# mainModule.net
KiCad netlist of a schematic drawn in EAGLE
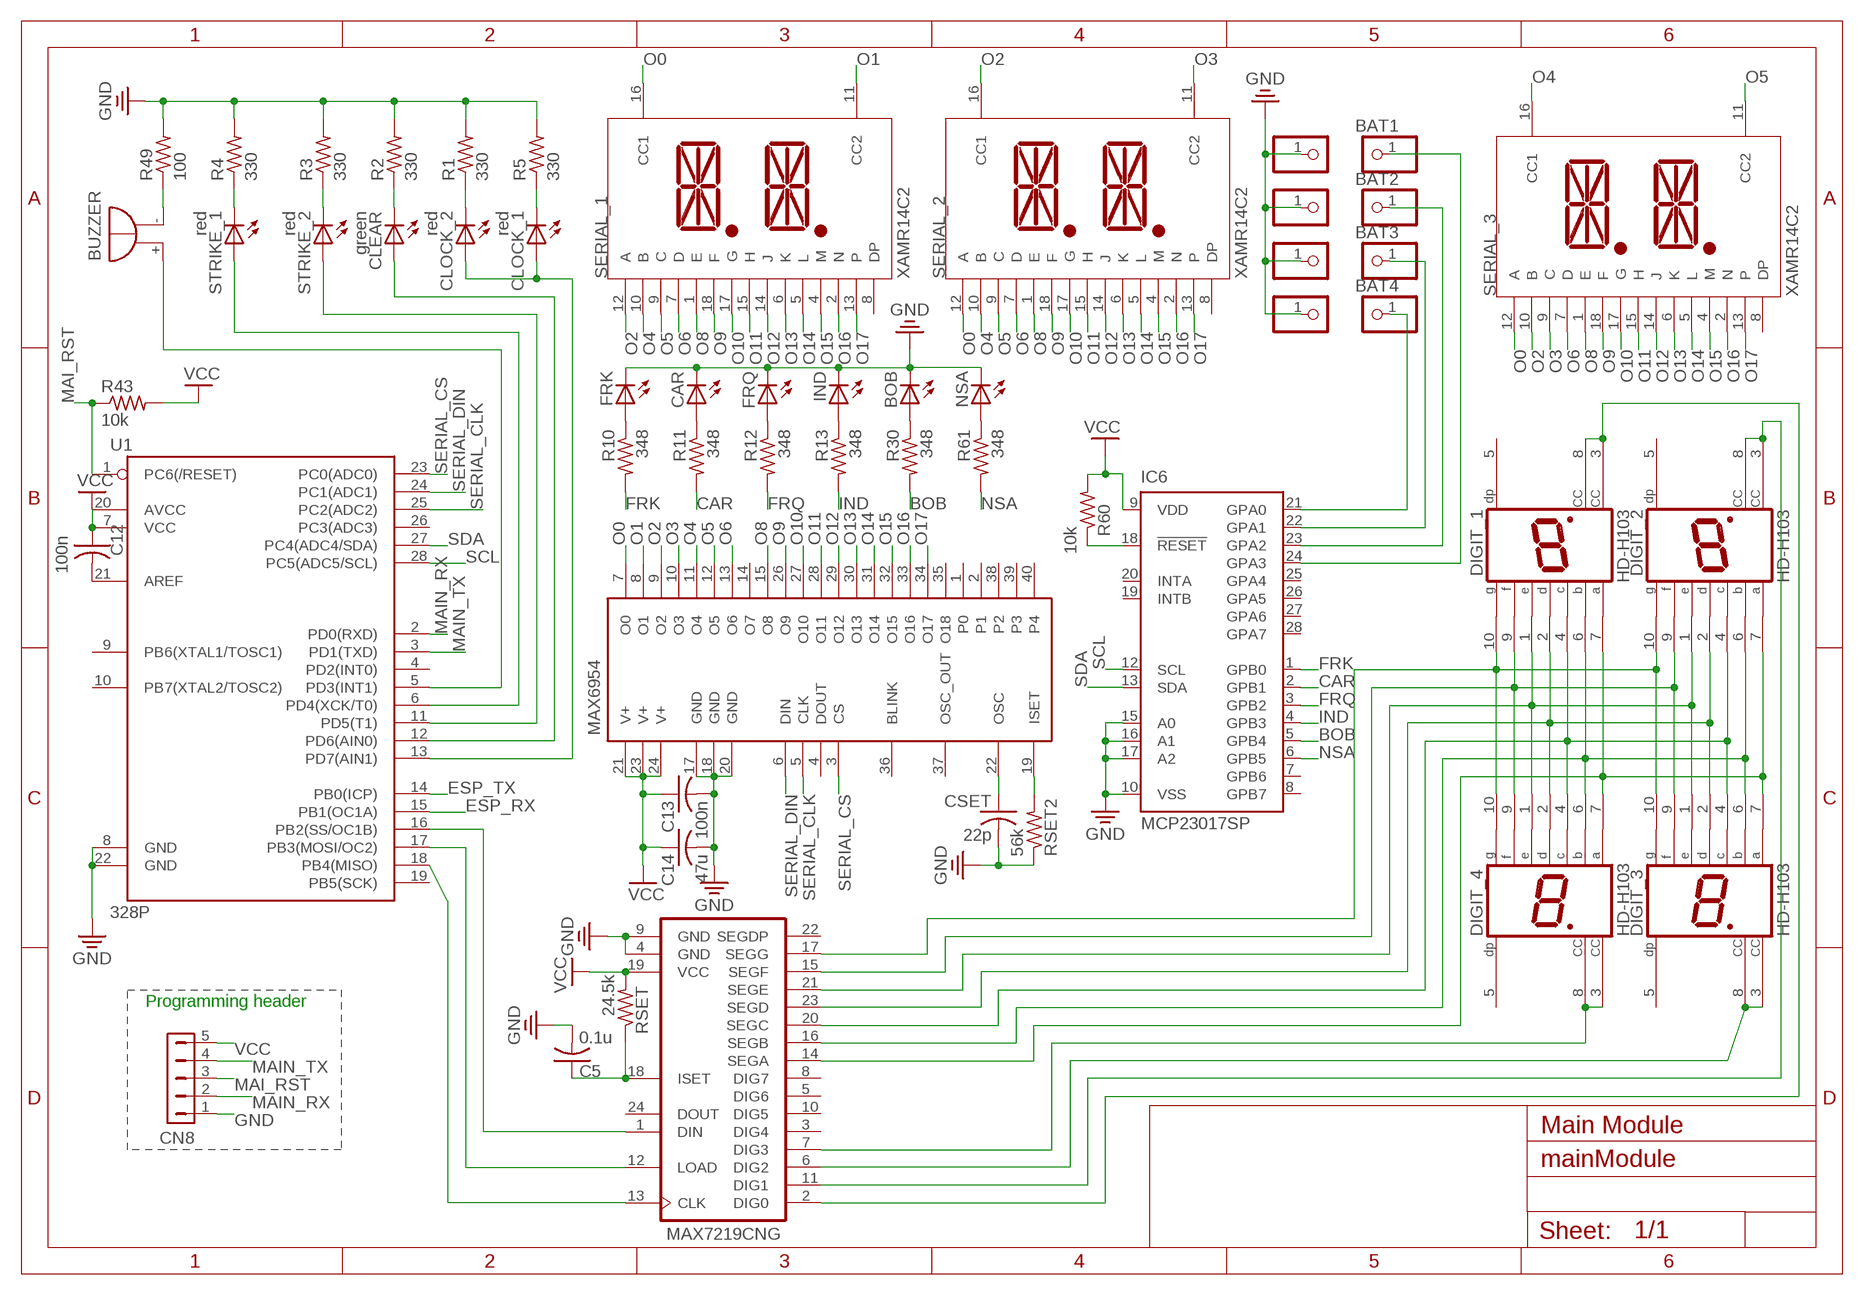
[diagram p0: schematic, sheet 1]

(export (version "E")
  (design (tool "Eeschema 10.0.6"))
  (components
    (comp (ref "BAT1")
      (value "PINHD-1X1")
      (footprint "eagle-import:1X01")
      (libsource (lib "eagle-import") (part "PINHD-1X1"))
    )
    (comp (ref "BAT2")
      (value "PINHD-1X1")
      (footprint "eagle-import:1X01")
      (libsource (lib "eagle-import") (part "PINHD-1X1"))
    )
    (comp (ref "BAT3")
      (value "PINHD-1X1")
      (footprint "eagle-import:1X01")
      (libsource (lib "eagle-import") (part "PINHD-1X1"))
    )
    (comp (ref "BAT4")
      (value "PINHD-1X1")
      (footprint "eagle-import:1X01")
      (libsource (lib "eagle-import") (part "PINHD-1X1"))
    )
    (comp (ref "BOB")
      (value "LED5MM")
      (footprint "eagle-import:LED5MM")
      (libsource (lib "eagle-import") (part "LED5MM"))
    )
    (comp (ref "BUZZER")
      (value "EB2209A")
      (footprint "eagle-import:EB2209A")
      (libsource (lib "eagle-import") (part "EB2209A"))
    )
    (comp (ref "C5")
      (value "0.1u")
      (footprint "eagle-import:C025-024X044")
      (libsource (lib "eagle-import") (part "C-US025-024X044"))
    )
    (comp (ref "C12")
      (value "100n")
      (footprint "eagle-import:C025-024X044")
      (libsource (lib "eagle-import") (part "C-US025-024X044"))
    )
    (comp (ref "C13")
      (value "100n")
      (footprint "eagle-import:C025-024X044")
      (libsource (lib "eagle-import") (part "C-US025-024X044"))
    )
    (comp (ref "C14")
      (value "47u")
      (footprint "eagle-import:C025-024X044")
      (libsource (lib "eagle-import") (part "C-US025-024X044"))
    )
    (comp (ref "CAR")
      (value "LED5MM")
      (footprint "eagle-import:LED5MM")
      (libsource (lib "eagle-import") (part "LED5MM"))
    )
    (comp (ref "CLEAR")
      (value "green")
      (footprint "eagle-import:LED5MM")
      (libsource (lib "eagle-import") (part "LED5MM"))
    )
    (comp (ref "CLOCK_1")
      (value "red")
      (footprint "eagle-import:LED5MM")
      (libsource (lib "eagle-import") (part "LED5MM"))
    )
    (comp (ref "CLOCK_2")
      (value "red")
      (footprint "eagle-import:LED5MM")
      (libsource (lib "eagle-import") (part "LED5MM"))
    )
    (comp (ref "CN8")
      (value "HDR-1X5-SIP-100")
      (footprint "eagle-import:SIP-100-5V")
      (libsource (lib "eagle-import") (part "HDR-1X5-SIP-100"))
    )
    (comp (ref "CSET")
      (value "22p")
      (footprint "eagle-import:C025-024X044")
      (libsource (lib "eagle-import") (part "C-US025-024X044"))
    )
    (comp (ref "DIGIT_1")
      (value "HD-H103")
      (footprint "eagle-import:HDSP-M")
      (libsource (lib "eagle-import") (part "HD-H103"))
    )
    (comp (ref "DIGIT_2")
      (value "HD-H103")
      (footprint "eagle-import:HDSP-M")
      (libsource (lib "eagle-import") (part "HD-H103"))
    )
    (comp (ref "DIGIT_3")
      (value "HD-H103")
      (footprint "eagle-import:HDSP-M")
      (libsource (lib "eagle-import") (part "HD-H103"))
    )
    (comp (ref "DIGIT_4")
      (value "HD-H103")
      (footprint "eagle-import:HDSP-M")
      (libsource (lib "eagle-import") (part "HD-H103"))
    )
    (comp (ref "FRK")
      (value "LED5MM")
      (footprint "eagle-import:LED5MM")
      (libsource (lib "eagle-import") (part "LED5MM"))
    )
    (comp (ref "FRQ")
      (value "LED5MM")
      (footprint "eagle-import:LED5MM")
      (libsource (lib "eagle-import") (part "LED5MM"))
    )
    (comp (ref "IC1")
      (value "MAX7219CNG")
      (footprint "eagle-import:DIL24-3")
      (fields (field (name "MF") "MAXIM"))
      (libsource (lib "eagle-import") (part "MAX7219CNG"))
    )
    (comp (ref "IC6")
      (value "MCP23017SP")
      (footprint "eagle-import:DIL28-3")
      (libsource (lib "eagle-import") (part "MCP23017SP"))
    )
    (comp (ref "IND")
      (value "LED5MM")
      (footprint "eagle-import:LED5MM")
      (libsource (lib "eagle-import") (part "LED5MM"))
    )
    (comp (ref "JP17")
      (value "PINHD-1X1")
      (footprint "eagle-import:1X01")
      (libsource (lib "eagle-import") (part "PINHD-1X1"))
    )
    (comp (ref "JP18")
      (value "PINHD-1X1")
      (footprint "eagle-import:1X01")
      (libsource (lib "eagle-import") (part "PINHD-1X1"))
    )
    (comp (ref "JP19")
      (value "PINHD-1X1")
      (footprint "eagle-import:1X01")
      (libsource (lib "eagle-import") (part "PINHD-1X1"))
    )
    (comp (ref "JP20")
      (value "PINHD-1X1")
      (footprint "eagle-import:1X01")
      (libsource (lib "eagle-import") (part "PINHD-1X1"))
    )
    (comp (ref "MAX6954")
      (value "MAX6954")
      (footprint "eagle-import:MAX6954")
      (libsource (lib "eagle-import") (part "MAX6954"))
    )
    (comp (ref "NSA")
      (value "LED5MM")
      (footprint "eagle-import:LED5MM")
      (libsource (lib "eagle-import") (part "LED5MM"))
    )
    (comp (ref "R1")
      (value "330")
      (footprint "eagle-import:0309_12")
      (libsource (lib "eagle-import") (part "adafruit_420_R-US_0309/12"))
    )
    (comp (ref "R2")
      (value "330")
      (footprint "eagle-import:0309_12")
      (libsource (lib "eagle-import") (part "adafruit_420_R-US_0309/12"))
    )
    (comp (ref "R3")
      (value "330")
      (footprint "eagle-import:0309_12")
      (libsource (lib "eagle-import") (part "adafruit_420_R-US_0309/12"))
    )
    (comp (ref "R4")
      (value "330")
      (footprint "eagle-import:0309_12")
      (libsource (lib "eagle-import") (part "adafruit_420_R-US_0309/12"))
    )
    (comp (ref "R5")
      (value "330")
      (footprint "eagle-import:0309_12")
      (libsource (lib "eagle-import") (part "adafruit_420_R-US_0309/12"))
    )
    (comp (ref "R10")
      (value "348")
      (footprint "eagle-import:0204_7")
      (libsource (lib "eagle-import") (part "R-US_0204/7"))
    )
    (comp (ref "R11")
      (value "348")
      (footprint "eagle-import:0204_7")
      (libsource (lib "eagle-import") (part "R-US_0204/7"))
    )
    (comp (ref "R12")
      (value "348")
      (footprint "eagle-import:0204_7")
      (libsource (lib "eagle-import") (part "R-US_0204/7"))
    )
    (comp (ref "R13")
      (value "348")
      (footprint "eagle-import:0204_7")
      (libsource (lib "eagle-import") (part "R-US_0204/7"))
    )
    (comp (ref "R30")
      (value "348")
      (footprint "eagle-import:0204_7")
      (libsource (lib "eagle-import") (part "R-US_0204/7"))
    )
    (comp (ref "R43")
      (value "10k")
      (footprint "eagle-import:0309_12")
      (libsource (lib "eagle-import") (part "adafruit_420_R-US_0309/12"))
    )
    (comp (ref "R49")
      (value "100")
      (footprint "eagle-import:0309_12")
      (libsource (lib "eagle-import") (part "adafruit_420_R-US_0309/12"))
    )
    (comp (ref "R60")
      (value "10k")
      (footprint "eagle-import:0204_7")
      (libsource (lib "eagle-import") (part "R-US_0204/7"))
    )
    (comp (ref "R61")
      (value "348")
      (footprint "eagle-import:0204_7")
      (libsource (lib "eagle-import") (part "R-US_0204/7"))
    )
    (comp (ref "RSET")
      (value "24.5k")
      (footprint "eagle-import:0204_7")
      (libsource (lib "eagle-import") (part "R-US_0204/7"))
    )
    (comp (ref "RSET2")
      (value "56k")
      (footprint "eagle-import:0204_7")
      (libsource (lib "eagle-import") (part "R-US_0204/7"))
    )
    (comp (ref "SERIAL_1")
      (value "XAMR14C2")
      (footprint "eagle-import:XAMR14C2")
      (libsource (lib "eagle-import") (part "XAMR14C2"))
    )
    (comp (ref "SERIAL_2")
      (value "XAMR14C2")
      (footprint "eagle-import:XAMR14C2")
      (libsource (lib "eagle-import") (part "XAMR14C2"))
    )
    (comp (ref "SERIAL_3")
      (value "XAMR14C2")
      (footprint "eagle-import:XAMR14C2")
      (libsource (lib "eagle-import") (part "XAMR14C2"))
    )
    (comp (ref "STRIKE_1")
      (value "red")
      (footprint "eagle-import:LED5MM")
      (libsource (lib "eagle-import") (part "LED5MM"))
    )
    (comp (ref "STRIKE_2")
      (value "red")
      (footprint "eagle-import:LED5MM")
      (libsource (lib "eagle-import") (part "LED5MM"))
    )
    (comp (ref "U1")
      (value "328P")
      (footprint "eagle-import:DIP28")
      (libsource (lib "eagle-import") (part "ATMEGA328P_PDIP"))
    )
  )
  (nets
    (net (code "1") (name "/BOB") (class "Default")
      (node (ref "IC6") (pin "5") (pinfunction "GPB4_5") (pintype "bidirectional"))
      (node (ref "R30") (pin "2") (pinfunction "2_2") (pintype "passive"))
    )
    (net (code "2") (name "/CAR") (class "Default")
      (node (ref "IC6") (pin "2") (pinfunction "GPB1_2") (pintype "bidirectional"))
      (node (ref "R11") (pin "2") (pinfunction "2_2") (pintype "passive"))
    )
    (net (code "3") (name "/ESP_RX") (class "Default")
      (node (ref "U1") (pin "15") (pinfunction "PB1(OC1A)_15") (pintype "bidirectional"))
    )
    (net (code "4") (name "/ESP_TX") (class "Default")
      (node (ref "U1") (pin "14") (pinfunction "PB0(ICP)_14") (pintype "bidirectional"))
    )
    (net (code "5") (name "/FRK") (class "Default")
      (node (ref "IC6") (pin "1") (pinfunction "GPB0_1") (pintype "bidirectional"))
      (node (ref "R10") (pin "2") (pinfunction "2_2") (pintype "passive"))
    )
    (net (code "6") (name "/FRQ") (class "Default")
      (node (ref "IC6") (pin "3") (pinfunction "GPB2_3") (pintype "bidirectional"))
      (node (ref "R12") (pin "2") (pinfunction "2_2") (pintype "passive"))
    )
    (net (code "7") (name "/IND") (class "Default")
      (node (ref "IC6") (pin "4") (pinfunction "GPB3_4") (pintype "bidirectional"))
      (node (ref "R13") (pin "2") (pinfunction "2_2") (pintype "passive"))
    )
    (net (code "8") (name "/MAIN_RX") (class "Default")
      (node (ref "CN8") (pin "2") (pinfunction "2_2") (pintype "passive"))
      (node (ref "U1") (pin "2") (pinfunction "PD0(RXD)_2") (pintype "bidirectional"))
    )
    (net (code "9") (name "/MAIN_TX") (class "Default")
      (node (ref "CN8") (pin "4") (pinfunction "4_4") (pintype "passive"))
      (node (ref "U1") (pin "3") (pinfunction "PD1(TXD)_3") (pintype "bidirectional"))
    )
    (net (code "10") (name "/MAI_RST") (class "Default")
      (node (ref "CN8") (pin "3") (pinfunction "3_3") (pintype "passive"))
      (node (ref "R43") (pin "1") (pinfunction "1_1") (pintype "passive"))
      (node (ref "U1") (pin "1") (pinfunction "PC6(/RESET)_1") (pintype "bidirectional"))
    )
    (net (code "11") (name "/NSA") (class "Default")
      (node (ref "IC6") (pin "6") (pinfunction "GPB5_6") (pintype "bidirectional"))
      (node (ref "R61") (pin "2") (pinfunction "2_2") (pintype "passive"))
    )
    (net (code "12") (name "/O0") (class "Default")
      (node (ref "MAX6954") (pin "7") (pinfunction "O0_7") (pintype "bidirectional"))
      (node (ref "SERIAL_1") (pin "16") (pinfunction "CC1_16") (pintype "bidirectional"))
      (node (ref "SERIAL_2") (pin "12") (pinfunction "A_12") (pintype "bidirectional"))
      (node (ref "SERIAL_3") (pin "12") (pinfunction "A_12") (pintype "bidirectional"))
    )
    (net (code "13") (name "/O1") (class "Default")
      (node (ref "MAX6954") (pin "8") (pinfunction "O1_8") (pintype "bidirectional"))
      (node (ref "SERIAL_1") (pin "11") (pinfunction "CC2_11") (pintype "bidirectional"))
    )
    (net (code "14") (name "/O2") (class "Default")
      (node (ref "MAX6954") (pin "9") (pinfunction "O2_9") (pintype "bidirectional"))
      (node (ref "SERIAL_1") (pin "12") (pinfunction "A_12") (pintype "bidirectional"))
      (node (ref "SERIAL_2") (pin "16") (pinfunction "CC1_16") (pintype "bidirectional"))
      (node (ref "SERIAL_3") (pin "10") (pinfunction "B_10") (pintype "bidirectional"))
    )
    (net (code "15") (name "/O3") (class "Default")
      (node (ref "MAX6954") (pin "10") (pinfunction "O3_10") (pintype "bidirectional"))
      (node (ref "SERIAL_2") (pin "11") (pinfunction "CC2_11") (pintype "bidirectional"))
      (node (ref "SERIAL_3") (pin "9") (pinfunction "C_9") (pintype "bidirectional"))
    )
    (net (code "16") (name "/O4") (class "Default")
      (node (ref "MAX6954") (pin "11") (pinfunction "O4_11") (pintype "bidirectional"))
      (node (ref "SERIAL_1") (pin "10") (pinfunction "B_10") (pintype "bidirectional"))
      (node (ref "SERIAL_2") (pin "10") (pinfunction "B_10") (pintype "bidirectional"))
      (node (ref "SERIAL_3") (pin "16") (pinfunction "CC1_16") (pintype "bidirectional"))
    )
    (net (code "17") (name "/O5") (class "Default")
      (node (ref "MAX6954") (pin "12") (pinfunction "O5_12") (pintype "bidirectional"))
      (node (ref "SERIAL_1") (pin "9") (pinfunction "C_9") (pintype "bidirectional"))
      (node (ref "SERIAL_2") (pin "9") (pinfunction "C_9") (pintype "bidirectional"))
      (node (ref "SERIAL_3") (pin "11") (pinfunction "CC2_11") (pintype "bidirectional"))
    )
    (net (code "18") (name "/O6") (class "Default")
      (node (ref "MAX6954") (pin "13") (pinfunction "O6_13") (pintype "bidirectional"))
      (node (ref "SERIAL_1") (pin "7") (pinfunction "D_7") (pintype "bidirectional"))
      (node (ref "SERIAL_2") (pin "7") (pinfunction "D_7") (pintype "bidirectional"))
      (node (ref "SERIAL_3") (pin "7") (pinfunction "D_7") (pintype "bidirectional"))
    )
    (net (code "19") (name "/O8") (class "Default")
      (node (ref "MAX6954") (pin "15") (pinfunction "O8_15") (pintype "bidirectional"))
      (node (ref "SERIAL_1") (pin "1") (pinfunction "E_1") (pintype "bidirectional"))
      (node (ref "SERIAL_2") (pin "1") (pinfunction "E_1") (pintype "bidirectional"))
      (node (ref "SERIAL_3") (pin "1") (pinfunction "E_1") (pintype "bidirectional"))
    )
    (net (code "20") (name "/O9") (class "Default")
      (node (ref "MAX6954") (pin "26") (pinfunction "O9_26") (pintype "bidirectional"))
      (node (ref "SERIAL_1") (pin "18") (pinfunction "F_18") (pintype "bidirectional"))
      (node (ref "SERIAL_2") (pin "18") (pinfunction "F_18") (pintype "bidirectional"))
      (node (ref "SERIAL_3") (pin "18") (pinfunction "F_18") (pintype "bidirectional"))
    )
    (net (code "21") (name "/O10") (class "Default")
      (node (ref "MAX6954") (pin "27") (pinfunction "O10_27") (pintype "bidirectional"))
      (node (ref "SERIAL_1") (pin "17") (pinfunction "G_17") (pintype "bidirectional"))
      (node (ref "SERIAL_2") (pin "17") (pinfunction "G_17") (pintype "bidirectional"))
      (node (ref "SERIAL_3") (pin "17") (pinfunction "G_17") (pintype "bidirectional"))
    )
    (net (code "22") (name "/O11") (class "Default")
      (node (ref "MAX6954") (pin "28") (pinfunction "O11_28") (pintype "bidirectional"))
      (node (ref "SERIAL_1") (pin "15") (pinfunction "H_15") (pintype "bidirectional"))
      (node (ref "SERIAL_2") (pin "15") (pinfunction "H_15") (pintype "bidirectional"))
      (node (ref "SERIAL_3") (pin "15") (pinfunction "H_15") (pintype "bidirectional"))
    )
    (net (code "23") (name "/O12") (class "Default")
      (node (ref "MAX6954") (pin "29") (pinfunction "O12_29") (pintype "bidirectional"))
      (node (ref "SERIAL_1") (pin "14") (pinfunction "J_14") (pintype "bidirectional"))
      (node (ref "SERIAL_2") (pin "14") (pinfunction "J_14") (pintype "bidirectional"))
      (node (ref "SERIAL_3") (pin "14") (pinfunction "J_14") (pintype "bidirectional"))
    )
    (net (code "24") (name "/O13") (class "Default")
      (node (ref "MAX6954") (pin "30") (pinfunction "O13_30") (pintype "bidirectional"))
      (node (ref "SERIAL_1") (pin "6") (pinfunction "K_6") (pintype "bidirectional"))
      (node (ref "SERIAL_2") (pin "6") (pinfunction "K_6") (pintype "bidirectional"))
      (node (ref "SERIAL_3") (pin "6") (pinfunction "K_6") (pintype "bidirectional"))
    )
    (net (code "25") (name "/O14") (class "Default")
      (node (ref "MAX6954") (pin "31") (pinfunction "O14_31") (pintype "bidirectional"))
      (node (ref "SERIAL_1") (pin "5") (pinfunction "L_5") (pintype "bidirectional"))
      (node (ref "SERIAL_2") (pin "5") (pinfunction "L_5") (pintype "bidirectional"))
      (node (ref "SERIAL_3") (pin "5") (pinfunction "L_5") (pintype "bidirectional"))
    )
    (net (code "26") (name "/O15") (class "Default")
      (node (ref "MAX6954") (pin "32") (pinfunction "O15_32") (pintype "bidirectional"))
      (node (ref "SERIAL_1") (pin "4") (pinfunction "M_4") (pintype "bidirectional"))
      (node (ref "SERIAL_2") (pin "4") (pinfunction "M_4") (pintype "bidirectional"))
      (node (ref "SERIAL_3") (pin "4") (pinfunction "M_4") (pintype "bidirectional"))
    )
    (net (code "27") (name "/O16") (class "Default")
      (node (ref "MAX6954") (pin "33") (pinfunction "O16_33") (pintype "bidirectional"))
      (node (ref "SERIAL_1") (pin "2") (pinfunction "N_2") (pintype "bidirectional"))
      (node (ref "SERIAL_2") (pin "2") (pinfunction "N_2") (pintype "bidirectional"))
      (node (ref "SERIAL_3") (pin "2") (pinfunction "N_2") (pintype "bidirectional"))
    )
    (net (code "28") (name "/O17") (class "Default")
      (node (ref "MAX6954") (pin "34") (pinfunction "O17_34") (pintype "bidirectional"))
      (node (ref "SERIAL_1") (pin "13") (pinfunction "P_13") (pintype "bidirectional"))
      (node (ref "SERIAL_2") (pin "13") (pinfunction "P_13") (pintype "bidirectional"))
      (node (ref "SERIAL_3") (pin "13") (pinfunction "P_13") (pintype "bidirectional"))
    )
    (net (code "29") (name "/SCL") (class "Default")
      (node (ref "IC6") (pin "12") (pinfunction "SCL_12") (pintype "input"))
      (node (ref "U1") (pin "28") (pinfunction "PC5(ADC5/SCL)_28") (pintype "bidirectional"))
    )
    (net (code "30") (name "/SDA") (class "Default")
      (node (ref "IC6") (pin "13") (pinfunction "SDA_13") (pintype "bidirectional"))
      (node (ref "U1") (pin "27") (pinfunction "PC4(ADC4/SDA)_27") (pintype "bidirectional"))
    )
    (net (code "31") (name "/SERIAL_CLK") (class "Default")
      (node (ref "MAX6954") (pin "5") (pinfunction "CLK_5") (pintype "bidirectional"))
      (node (ref "U1") (pin "25") (pinfunction "PC2(ADC2)_25") (pintype "bidirectional"))
    )
    (net (code "32") (name "/SERIAL_CS") (class "Default")
      (node (ref "MAX6954") (pin "3") (pinfunction "CS_3") (pintype "bidirectional"))
      (node (ref "U1") (pin "23") (pinfunction "PC0(ADC0)_23") (pintype "bidirectional"))
    )
    (net (code "33") (name "/SERIAL_DIN") (class "Default")
      (node (ref "MAX6954") (pin "6") (pinfunction "DIN_6") (pintype "bidirectional"))
      (node (ref "U1") (pin "24") (pinfunction "PC1(ADC1)_24") (pintype "bidirectional"))
    )
    (net (code "34") (name "GND") (class "Default")
      (node (ref "BOB") (pin "K") (pinfunction "C_K") (pintype "passive"))
      (node (ref "C13") (pin "2") (pinfunction "2_2") (pintype "passive"))
      (node (ref "C14") (pin "2") (pinfunction "2_2") (pintype "passive"))
      (node (ref "C5") (pin "2") (pinfunction "2_2") (pintype "passive"))
      (node (ref "CAR") (pin "K") (pinfunction "C_K") (pintype "passive"))
      (node (ref "CN8") (pin "1") (pinfunction "1_1") (pintype "passive"))
      (node (ref "CSET") (pin "2") (pinfunction "2_2") (pintype "passive"))
      (node (ref "FRK") (pin "K") (pinfunction "C_K") (pintype "passive"))
      (node (ref "FRQ") (pin "K") (pinfunction "C_K") (pintype "passive"))
      (node (ref "IC1") (pin "4") (pinfunction "GND_4") (pintype "power_in"))
      (node (ref "IC1") (pin "9") (pinfunction "GND_9") (pintype "power_in"))
      (node (ref "IC6") (pin "10") (pinfunction "VSS_10") (pintype "power_in"))
      (node (ref "IC6") (pin "15") (pinfunction "A0_15") (pintype "input"))
      (node (ref "IC6") (pin "16") (pinfunction "A1_16") (pintype "input"))
      (node (ref "IC6") (pin "17") (pinfunction "A2_17") (pintype "input"))
      (node (ref "IND") (pin "K") (pinfunction "C_K") (pintype "passive"))
      (node (ref "JP17") (pin "1") (pinfunction "1_1") (pintype "passive"))
      (node (ref "JP18") (pin "1") (pinfunction "1_1") (pintype "passive"))
      (node (ref "JP19") (pin "1") (pinfunction "1_1") (pintype "passive"))
      (node (ref "JP20") (pin "1") (pinfunction "1_1") (pintype "passive"))
      (node (ref "MAX6954") (pin "17") (pinfunction "GND_17") (pintype "bidirectional"))
      (node (ref "MAX6954") (pin "18") (pinfunction "GND_18") (pintype "bidirectional"))
      (node (ref "MAX6954") (pin "20") (pinfunction "GND_20") (pintype "bidirectional"))
      (node (ref "NSA") (pin "K") (pinfunction "C_K") (pintype "passive"))
      (node (ref "R1") (pin "2") (pinfunction "2_2") (pintype "passive"))
      (node (ref "R2") (pin "2") (pinfunction "2_2") (pintype "passive"))
      (node (ref "R3") (pin "2") (pinfunction "2_2") (pintype "passive"))
      (node (ref "R4") (pin "2") (pinfunction "2_2") (pintype "passive"))
      (node (ref "R49") (pin "2") (pinfunction "2_2") (pintype "passive"))
      (node (ref "R5") (pin "2") (pinfunction "2_2") (pintype "passive"))
      (node (ref "RSET2") (pin "1") (pinfunction "1_1") (pintype "passive"))
      (node (ref "U1") (pin "22") (pinfunction "GND_22") (pintype "bidirectional"))
      (node (ref "U1") (pin "8") (pinfunction "GND_8") (pintype "bidirectional"))
    )
    (net (code "35") (name "Net-(BOB-PadA)") (class "Default")
      (node (ref "BOB") (pin "A") (pinfunction "A_A") (pintype "passive"))
      (node (ref "R30") (pin "1") (pinfunction "1_1") (pintype "passive"))
    )
    (net (code "36") (name "Net-(BUZZER-Pad-)") (class "Default")
      (node (ref "BUZZER") (pin "-") (pinfunction "-_-") (pintype "passive"))
      (node (ref "R49") (pin "1") (pinfunction "1_1") (pintype "passive"))
    )
    (net (code "37") (name "Net-(CAR-PadA)") (class "Default")
      (node (ref "CAR") (pin "A") (pinfunction "A_A") (pintype "passive"))
      (node (ref "R11") (pin "1") (pinfunction "1_1") (pintype "passive"))
    )
    (net (code "38") (name "Net-(CLEAR-C)") (class "Default")
      (node (ref "CLEAR") (pin "K") (pinfunction "C_K") (pintype "passive"))
      (node (ref "R2") (pin "1") (pinfunction "1_1") (pintype "passive"))
    )
    (net (code "39") (name "Net-(CLOCK_1-C)") (class "Default")
      (node (ref "CLOCK_1") (pin "K") (pinfunction "C_K") (pintype "passive"))
      (node (ref "R5") (pin "1") (pinfunction "1_1") (pintype "passive"))
    )
    (net (code "40") (name "Net-(CLOCK_2-C)") (class "Default")
      (node (ref "CLOCK_2") (pin "K") (pinfunction "C_K") (pintype "passive"))
      (node (ref "R1") (pin "1") (pinfunction "1_1") (pintype "passive"))
    )
    (net (code "41") (name "Net-(DIGIT_1-A)") (class "Default")
      (node (ref "DIGIT_1") (pin "7") (pinfunction "A_7") (pintype "passive"))
      (node (ref "DIGIT_2") (pin "7") (pinfunction "A_7") (pintype "passive"))
      (node (ref "DIGIT_3") (pin "7") (pinfunction "A_7") (pintype "passive"))
      (node (ref "DIGIT_4") (pin "7") (pinfunction "A_7") (pintype "passive"))
      (node (ref "IC1") (pin "14") (pinfunction "SEGA_14") (pintype "output"))
    )
    (net (code "42") (name "Net-(DIGIT_1-B)") (class "Default")
      (node (ref "DIGIT_1") (pin "6") (pinfunction "B_6") (pintype "passive"))
      (node (ref "DIGIT_2") (pin "6") (pinfunction "B_6") (pintype "passive"))
      (node (ref "DIGIT_3") (pin "6") (pinfunction "B_6") (pintype "passive"))
      (node (ref "DIGIT_4") (pin "6") (pinfunction "B_6") (pintype "passive"))
      (node (ref "IC1") (pin "16") (pinfunction "SEGB_16") (pintype "output"))
    )
    (net (code "43") (name "Net-(DIGIT_1-C)") (class "Default")
      (node (ref "DIGIT_1") (pin "4") (pinfunction "C_4") (pintype "passive"))
      (node (ref "DIGIT_2") (pin "4") (pinfunction "C_4") (pintype "passive"))
      (node (ref "DIGIT_3") (pin "4") (pinfunction "C_4") (pintype "passive"))
      (node (ref "DIGIT_4") (pin "4") (pinfunction "C_4") (pintype "passive"))
      (node (ref "IC1") (pin "20") (pinfunction "SEGC_20") (pintype "output"))
    )
    (net (code "44") (name "Net-(DIGIT_1-D)") (class "Default")
      (node (ref "DIGIT_1") (pin "2") (pinfunction "D_2") (pintype "passive"))
      (node (ref "DIGIT_2") (pin "2") (pinfunction "D_2") (pintype "passive"))
      (node (ref "DIGIT_3") (pin "2") (pinfunction "D_2") (pintype "passive"))
      (node (ref "DIGIT_4") (pin "2") (pinfunction "D_2") (pintype "passive"))
      (node (ref "IC1") (pin "23") (pinfunction "SEGD_23") (pintype "output"))
    )
    (net (code "45") (name "Net-(DIGIT_1-E)") (class "Default")
      (node (ref "DIGIT_1") (pin "1") (pinfunction "E_1") (pintype "passive"))
      (node (ref "DIGIT_2") (pin "1") (pinfunction "E_1") (pintype "passive"))
      (node (ref "DIGIT_3") (pin "1") (pinfunction "E_1") (pintype "passive"))
      (node (ref "DIGIT_4") (pin "1") (pinfunction "E_1") (pintype "passive"))
      (node (ref "IC1") (pin "21") (pinfunction "SEGE_21") (pintype "output"))
    )
    (net (code "46") (name "Net-(DIGIT_1-F)") (class "Default")
      (node (ref "DIGIT_1") (pin "9") (pinfunction "F_9") (pintype "passive"))
      (node (ref "DIGIT_2") (pin "9") (pinfunction "F_9") (pintype "passive"))
      (node (ref "DIGIT_3") (pin "9") (pinfunction "F_9") (pintype "passive"))
      (node (ref "DIGIT_4") (pin "9") (pinfunction "F_9") (pintype "passive"))
      (node (ref "IC1") (pin "15") (pinfunction "SEGF_15") (pintype "output"))
    )
    (net (code "47") (name "Net-(DIGIT_1-G)") (class "Default")
      (node (ref "DIGIT_1") (pin "10") (pinfunction "G_10") (pintype "passive"))
      (node (ref "DIGIT_2") (pin "10") (pinfunction "G_10") (pintype "passive"))
      (node (ref "DIGIT_3") (pin "10") (pinfunction "G_10") (pintype "passive"))
      (node (ref "DIGIT_4") (pin "10") (pinfunction "G_10") (pintype "passive"))
      (node (ref "IC1") (pin "17") (pinfunction "SEGG_17") (pintype "output"))
    )
    (net (code "48") (name "Net-(FRK-PadA)") (class "Default")
      (node (ref "FRK") (pin "A") (pinfunction "A_A") (pintype "passive"))
      (node (ref "R10") (pin "1") (pinfunction "1_1") (pintype "passive"))
    )
    (net (code "49") (name "Net-(FRQ-PadA)") (class "Default")
      (node (ref "FRQ") (pin "A") (pinfunction "A_A") (pintype "passive"))
      (node (ref "R12") (pin "1") (pinfunction "1_1") (pintype "passive"))
    )
    (net (code "50") (name "Net-(IC1-CLK)") (class "Default")
      (node (ref "IC1") (pin "13") (pinfunction "CLK_13") (pintype "input"))
      (node (ref "U1") (pin "18") (pinfunction "PB4(MISO)_18") (pintype "bidirectional"))
    )
    (net (code "51") (name "Net-(IC1-DIG0)") (class "Default")
      (node (ref "DIGIT_1") (pin "3") (pinfunction "CC_3") (pintype "passive"))
      (node (ref "DIGIT_1") (pin "8") (pinfunction "CC_8") (pintype "passive"))
      (node (ref "IC1") (pin "2") (pinfunction "DIG0_2") (pintype "output"))
    )
    (net (code "52") (name "Net-(IC1-DIG1)") (class "Default")
      (node (ref "DIGIT_2") (pin "3") (pinfunction "CC_3") (pintype "passive"))
      (node (ref "DIGIT_2") (pin "8") (pinfunction "CC_8") (pintype "passive"))
      (node (ref "IC1") (pin "11") (pinfunction "DIG1_11") (pintype "output"))
    )
    (net (code "53") (name "Net-(IC1-DIG2)") (class "Default")
      (node (ref "DIGIT_3") (pin "3") (pinfunction "CC_3") (pintype "passive"))
      (node (ref "DIGIT_3") (pin "8") (pinfunction "CC_8") (pintype "passive"))
      (node (ref "IC1") (pin "6") (pinfunction "DIG2_6") (pintype "output"))
    )
    (net (code "54") (name "Net-(IC1-DIG3)") (class "Default")
      (node (ref "DIGIT_4") (pin "3") (pinfunction "CC_3") (pintype "passive"))
      (node (ref "DIGIT_4") (pin "8") (pinfunction "CC_8") (pintype "passive"))
      (node (ref "IC1") (pin "7") (pinfunction "DIG3_7") (pintype "output"))
    )
    (net (code "55") (name "Net-(IC1-DIN)") (class "Default")
      (node (ref "IC1") (pin "1") (pinfunction "DIN_1") (pintype "input"))
      (node (ref "U1") (pin "16") (pinfunction "PB2(SS/OC1B)_16") (pintype "bidirectional"))
    )
    (net (code "56") (name "Net-(IC1-ISET)") (class "Default")
      (node (ref "C5") (pin "1") (pinfunction "1_1") (pintype "passive"))
      (node (ref "IC1") (pin "18") (pinfunction "ISET_18") (pintype "input"))
      (node (ref "RSET") (pin "1") (pinfunction "1_1") (pintype "passive"))
    )
    (net (code "57") (name "Net-(IC1-LOAD)") (class "Default")
      (node (ref "IC1") (pin "12") (pinfunction "LOAD_12") (pintype "input"))
      (node (ref "U1") (pin "17") (pinfunction "PB3(MOSI/OC2)_17") (pintype "bidirectional"))
    )
    (net (code "58") (name "Net-(IC6-GPA0)") (class "Default")
      (node (ref "BAT4") (pin "1") (pinfunction "1_1") (pintype "passive"))
      (node (ref "IC6") (pin "21") (pinfunction "GPA0_21") (pintype "bidirectional"))
    )
    (net (code "59") (name "Net-(IC6-GPA1)") (class "Default")
      (node (ref "BAT3") (pin "1") (pinfunction "1_1") (pintype "passive"))
      (node (ref "IC6") (pin "22") (pinfunction "GPA1_22") (pintype "bidirectional"))
    )
    (net (code "60") (name "Net-(IC6-GPA2)") (class "Default")
      (node (ref "BAT2") (pin "1") (pinfunction "1_1") (pintype "passive"))
      (node (ref "IC6") (pin "23") (pinfunction "GPA2_23") (pintype "bidirectional"))
    )
    (net (code "61") (name "Net-(IC6-GPA3)") (class "Default")
      (node (ref "BAT1") (pin "1") (pinfunction "1_1") (pintype "passive"))
      (node (ref "IC6") (pin "24") (pinfunction "GPA3_24") (pintype "bidirectional"))
    )
    (net (code "62") (name "Net-(IC6-~{RESET})") (class "Default")
      (node (ref "IC6") (pin "18") (pinfunction "~{RESET}_18") (pintype "input"))
      (node (ref "R60") (pin "1") (pinfunction "1_1") (pintype "passive"))
    )
    (net (code "63") (name "Net-(IND-PadA)") (class "Default")
      (node (ref "IND") (pin "A") (pinfunction "A_A") (pintype "passive"))
      (node (ref "R13") (pin "1") (pinfunction "1_1") (pintype "passive"))
    )
    (net (code "64") (name "Net-(MAX6954-ISET)") (class "Default")
      (node (ref "MAX6954") (pin "19") (pinfunction "ISET_19") (pintype "bidirectional"))
      (node (ref "RSET2") (pin "2") (pinfunction "2_2") (pintype "passive"))
    )
    (net (code "65") (name "Net-(MAX6954-OSC)") (class "Default")
      (node (ref "CSET") (pin "1") (pinfunction "1_1") (pintype "passive"))
      (node (ref "MAX6954") (pin "22") (pinfunction "OSC_22") (pintype "bidirectional"))
    )
    (net (code "66") (name "Net-(NSA-PadA)") (class "Default")
      (node (ref "NSA") (pin "A") (pinfunction "A_A") (pintype "passive"))
      (node (ref "R61") (pin "1") (pinfunction "1_1") (pintype "passive"))
    )
    (net (code "67") (name "Net-(STRIKE_1-C)") (class "Default")
      (node (ref "R4") (pin "1") (pinfunction "1_1") (pintype "passive"))
      (node (ref "STRIKE_1") (pin "K") (pinfunction "C_K") (pintype "passive"))
    )
    (net (code "68") (name "Net-(STRIKE_2-C)") (class "Default")
      (node (ref "R3") (pin "1") (pinfunction "1_1") (pintype "passive"))
      (node (ref "STRIKE_2") (pin "K") (pinfunction "C_K") (pintype "passive"))
    )
    (net (code "69") (name "Net-(U1-AREF)") (class "Default")
      (node (ref "C12") (pin "2") (pinfunction "2_2") (pintype "passive"))
      (node (ref "U1") (pin "21") (pinfunction "AREF_21") (pintype "bidirectional"))
    )
    (net (code "70") (name "Net-(U1-PD3(INT1))") (class "Default")
      (node (ref "BUZZER") (pin "+") (pinfunction "+_+") (pintype "passive"))
      (node (ref "U1") (pin "5") (pinfunction "PD3(INT1)_5") (pintype "bidirectional"))
    )
    (net (code "71") (name "Net-(U1-PD4(XCK{slash}T0))") (class "Default")
      (node (ref "STRIKE_1") (pin "A") (pinfunction "A_A") (pintype "passive"))
      (node (ref "U1") (pin "6") (pinfunction "PD4(XCK/T0)_6") (pintype "bidirectional"))
    )
    (net (code "72") (name "Net-(U1-PD5(T1))") (class "Default")
      (node (ref "STRIKE_2") (pin "A") (pinfunction "A_A") (pintype "passive"))
      (node (ref "U1") (pin "11") (pinfunction "PD5(T1)_11") (pintype "bidirectional"))
    )
    (net (code "73") (name "Net-(U1-PD6(AIN0))") (class "Default")
      (node (ref "CLEAR") (pin "A") (pinfunction "A_A") (pintype "passive"))
      (node (ref "U1") (pin "12") (pinfunction "PD6(AIN0)_12") (pintype "bidirectional"))
    )
    (net (code "74") (name "Net-(U1-PD7(AIN1))") (class "Default")
      (node (ref "CLOCK_1") (pin "A") (pinfunction "A_A") (pintype "passive"))
      (node (ref "CLOCK_2") (pin "A") (pinfunction "A_A") (pintype "passive"))
      (node (ref "U1") (pin "13") (pinfunction "PD7(AIN1)_13") (pintype "bidirectional"))
    )
    (net (code "75") (name "VCC") (class "Default")
      (node (ref "C12") (pin "1") (pinfunction "1_1") (pintype "passive"))
      (node (ref "C13") (pin "1") (pinfunction "1_1") (pintype "passive"))
      (node (ref "C14") (pin "1") (pinfunction "1_1") (pintype "passive"))
      (node (ref "CN8") (pin "5") (pinfunction "5_5") (pintype "passive"))
      (node (ref "IC1") (pin "19") (pinfunction "VCC_19") (pintype "power_in"))
      (node (ref "IC6") (pin "9") (pinfunction "VDD_9") (pintype "power_in"))
      (node (ref "MAX6954") (pin "21") (pinfunction "V+_21") (pintype "power_in"))
      (node (ref "MAX6954") (pin "23") (pinfunction "V+_23") (pintype "power_in"))
      (node (ref "MAX6954") (pin "24") (pinfunction "V+_24") (pintype "power_in"))
      (node (ref "R43") (pin "2") (pinfunction "2_2") (pintype "passive"))
      (node (ref "R60") (pin "2") (pinfunction "2_2") (pintype "passive"))
      (node (ref "RSET") (pin "2") (pinfunction "2_2") (pintype "passive"))
      (node (ref "U1") (pin "20") (pinfunction "AVCC_20") (pintype "bidirectional"))
      (node (ref "U1") (pin "7") (pinfunction "VCC_7") (pintype "bidirectional"))
    )
    (net (code "76") (name "unconnected-(DIGIT_1-DP-Pad5)") (class "Default")
      (node (ref "DIGIT_1") (pin "5") (pinfunction "DP_5") (pintype "passive"))
    )
    (net (code "77") (name "unconnected-(DIGIT_2-DP-Pad5)") (class "Default")
      (node (ref "DIGIT_2") (pin "5") (pinfunction "DP_5") (pintype "passive"))
    )
    (net (code "78") (name "unconnected-(DIGIT_3-DP-Pad5)") (class "Default")
      (node (ref "DIGIT_3") (pin "5") (pinfunction "DP_5") (pintype "passive"))
    )
    (net (code "79") (name "unconnected-(DIGIT_4-DP-Pad5)") (class "Default")
      (node (ref "DIGIT_4") (pin "5") (pinfunction "DP_5") (pintype "passive"))
    )
    (net (code "80") (name "unconnected-(IC1-DIG4-Pad3)") (class "Default")
      (node (ref "IC1") (pin "3") (pinfunction "DIG4_3") (pintype "output"))
    )
    (net (code "81") (name "unconnected-(IC1-DIG5-Pad10)") (class "Default")
      (node (ref "IC1") (pin "10") (pinfunction "DIG5_10") (pintype "output"))
    )
    (net (code "82") (name "unconnected-(IC1-DIG6-Pad5)") (class "Default")
      (node (ref "IC1") (pin "5") (pinfunction "DIG6_5") (pintype "output"))
    )
    (net (code "83") (name "unconnected-(IC1-DIG7-Pad8)") (class "Default")
      (node (ref "IC1") (pin "8") (pinfunction "DIG7_8") (pintype "output"))
    )
    (net (code "84") (name "unconnected-(IC1-DOUT-Pad24)") (class "Default")
      (node (ref "IC1") (pin "24") (pinfunction "DOUT_24") (pintype "output"))
    )
    (net (code "85") (name "unconnected-(IC1-SEGDP-Pad22)") (class "Default")
      (node (ref "IC1") (pin "22") (pinfunction "SEGDP_22") (pintype "output"))
    )
    (net (code "86") (name "unconnected-(IC6-GPA4-Pad25)") (class "Default")
      (node (ref "IC6") (pin "25") (pinfunction "GPA4_25") (pintype "bidirectional"))
    )
    (net (code "87") (name "unconnected-(IC6-GPA5-Pad26)") (class "Default")
      (node (ref "IC6") (pin "26") (pinfunction "GPA5_26") (pintype "bidirectional"))
    )
    (net (code "88") (name "unconnected-(IC6-GPA6-Pad27)") (class "Default")
      (node (ref "IC6") (pin "27") (pinfunction "GPA6_27") (pintype "bidirectional"))
    )
    (net (code "89") (name "unconnected-(IC6-GPA7-Pad28)") (class "Default")
      (node (ref "IC6") (pin "28") (pinfunction "GPA7_28") (pintype "bidirectional"))
    )
    (net (code "90") (name "unconnected-(IC6-GPB6-Pad7)") (class "Default")
      (node (ref "IC6") (pin "7") (pinfunction "GPB6_7") (pintype "bidirectional"))
    )
    (net (code "91") (name "unconnected-(IC6-GPB7-Pad8)") (class "Default")
      (node (ref "IC6") (pin "8") (pinfunction "GPB7_8") (pintype "bidirectional"))
    )
    (net (code "92") (name "unconnected-(IC6-INTA-Pad20)") (class "Default")
      (node (ref "IC6") (pin "20") (pinfunction "INTA_20") (pintype "output"))
    )
    (net (code "93") (name "unconnected-(IC6-INTB-Pad19)") (class "Default")
      (node (ref "IC6") (pin "19") (pinfunction "INTB_19") (pintype "output"))
    )
    (net (code "94") (name "unconnected-(MAX6954-BLINK-Pad36)") (class "Default")
      (node (ref "MAX6954") (pin "36") (pinfunction "BLINK_36") (pintype "bidirectional"))
    )
    (net (code "95") (name "unconnected-(MAX6954-DOUT-Pad4)") (class "Default")
      (node (ref "MAX6954") (pin "4") (pinfunction "DOUT_4") (pintype "bidirectional"))
    )
    (net (code "96") (name "unconnected-(MAX6954-O7-Pad14)") (class "Default")
      (node (ref "MAX6954") (pin "14") (pinfunction "O7_14") (pintype "bidirectional"))
    )
    (net (code "97") (name "unconnected-(MAX6954-O18-Pad35)") (class "Default")
      (node (ref "MAX6954") (pin "35") (pinfunction "O18_35") (pintype "bidirectional"))
    )
    (net (code "98") (name "unconnected-(MAX6954-OSC_OUT-Pad37)") (class "Default")
      (node (ref "MAX6954") (pin "37") (pinfunction "OSC_OUT_37") (pintype "bidirectional"))
    )
    (net (code "99") (name "unconnected-(MAX6954-P0-Pad1)") (class "Default")
      (node (ref "MAX6954") (pin "1") (pinfunction "P0_1") (pintype "bidirectional"))
    )
    (net (code "100") (name "unconnected-(MAX6954-P1-Pad2)") (class "Default")
      (node (ref "MAX6954") (pin "2") (pinfunction "P1_2") (pintype "bidirectional"))
    )
    (net (code "101") (name "unconnected-(MAX6954-P2-Pad38)") (class "Default")
      (node (ref "MAX6954") (pin "38") (pinfunction "P2_38") (pintype "bidirectional"))
    )
    (net (code "102") (name "unconnected-(MAX6954-P3-Pad39)") (class "Default")
      (node (ref "MAX6954") (pin "39") (pinfunction "P3_39") (pintype "bidirectional"))
    )
    (net (code "103") (name "unconnected-(MAX6954-P4-Pad40)") (class "Default")
      (node (ref "MAX6954") (pin "40") (pinfunction "P4_40") (pintype "bidirectional"))
    )
    (net (code "104") (name "unconnected-(SERIAL_1-DP-Pad8)") (class "Default")
      (node (ref "SERIAL_1") (pin "8") (pinfunction "DP_8") (pintype "bidirectional"))
    )
    (net (code "105") (name "unconnected-(SERIAL_2-DP-Pad8)") (class "Default")
      (node (ref "SERIAL_2") (pin "8") (pinfunction "DP_8") (pintype "bidirectional"))
    )
    (net (code "106") (name "unconnected-(SERIAL_3-DP-Pad8)") (class "Default")
      (node (ref "SERIAL_3") (pin "8") (pinfunction "DP_8") (pintype "bidirectional"))
    )
    (net (code "107") (name "unconnected-(U1-PB5(SCK)-Pad19)") (class "Default")
      (node (ref "U1") (pin "19") (pinfunction "PB5(SCK)_19") (pintype "bidirectional"))
    )
    (net (code "108") (name "unconnected-(U1-PB6(XTAL1{slash}TOSC1)-Pad9)") (class "Default")
      (node (ref "U1") (pin "9") (pinfunction "PB6(XTAL1/TOSC1)_9") (pintype "bidirectional"))
    )
    (net (code "109") (name "unconnected-(U1-PB7(XTAL2{slash}TOSC2)-Pad10)") (class "Default")
      (node (ref "U1") (pin "10") (pinfunction "PB7(XTAL2/TOSC2)_10") (pintype "bidirectional"))
    )
    (net (code "110") (name "unconnected-(U1-PC3(ADC3)-Pad26)") (class "Default")
      (node (ref "U1") (pin "26") (pinfunction "PC3(ADC3)_26") (pintype "bidirectional"))
    )
    (net (code "111") (name "unconnected-(U1-PD2(INT0)-Pad4)") (class "Default")
      (node (ref "U1") (pin "4") (pinfunction "PD2(INT0)_4") (pintype "bidirectional"))
    )
  )
)
